# robot.net
KiCad netlist of a schematic drawn in EAGLE
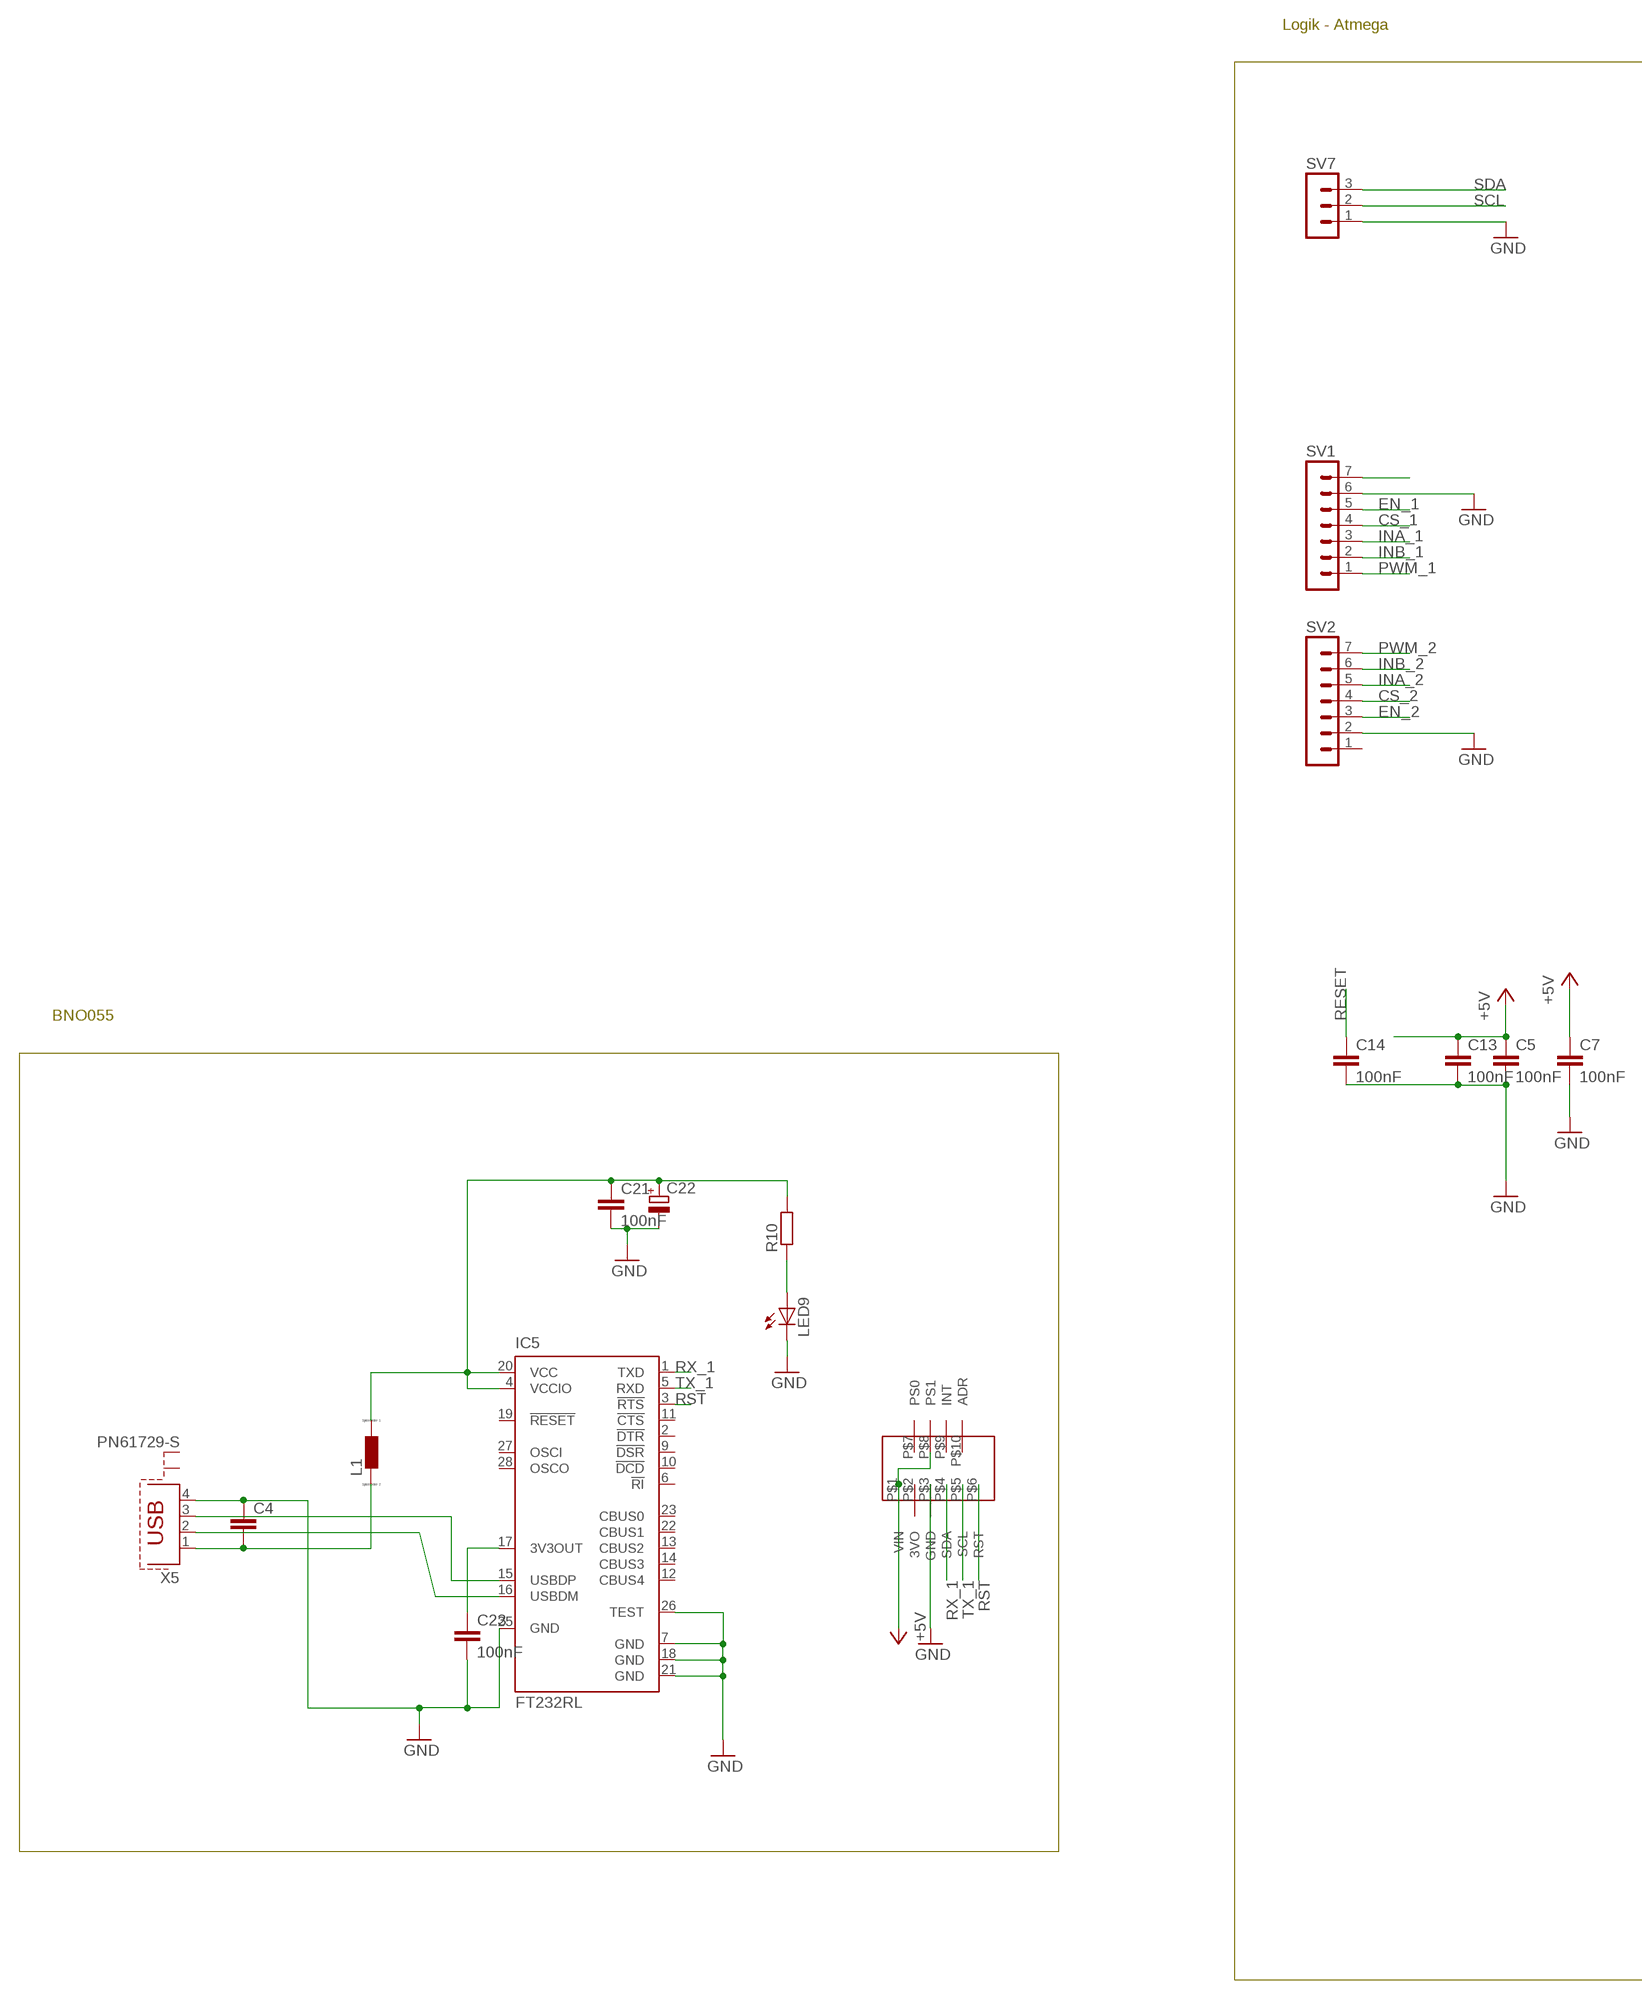
[diagram p0: schematic, sheet 1, part 1 of 3]
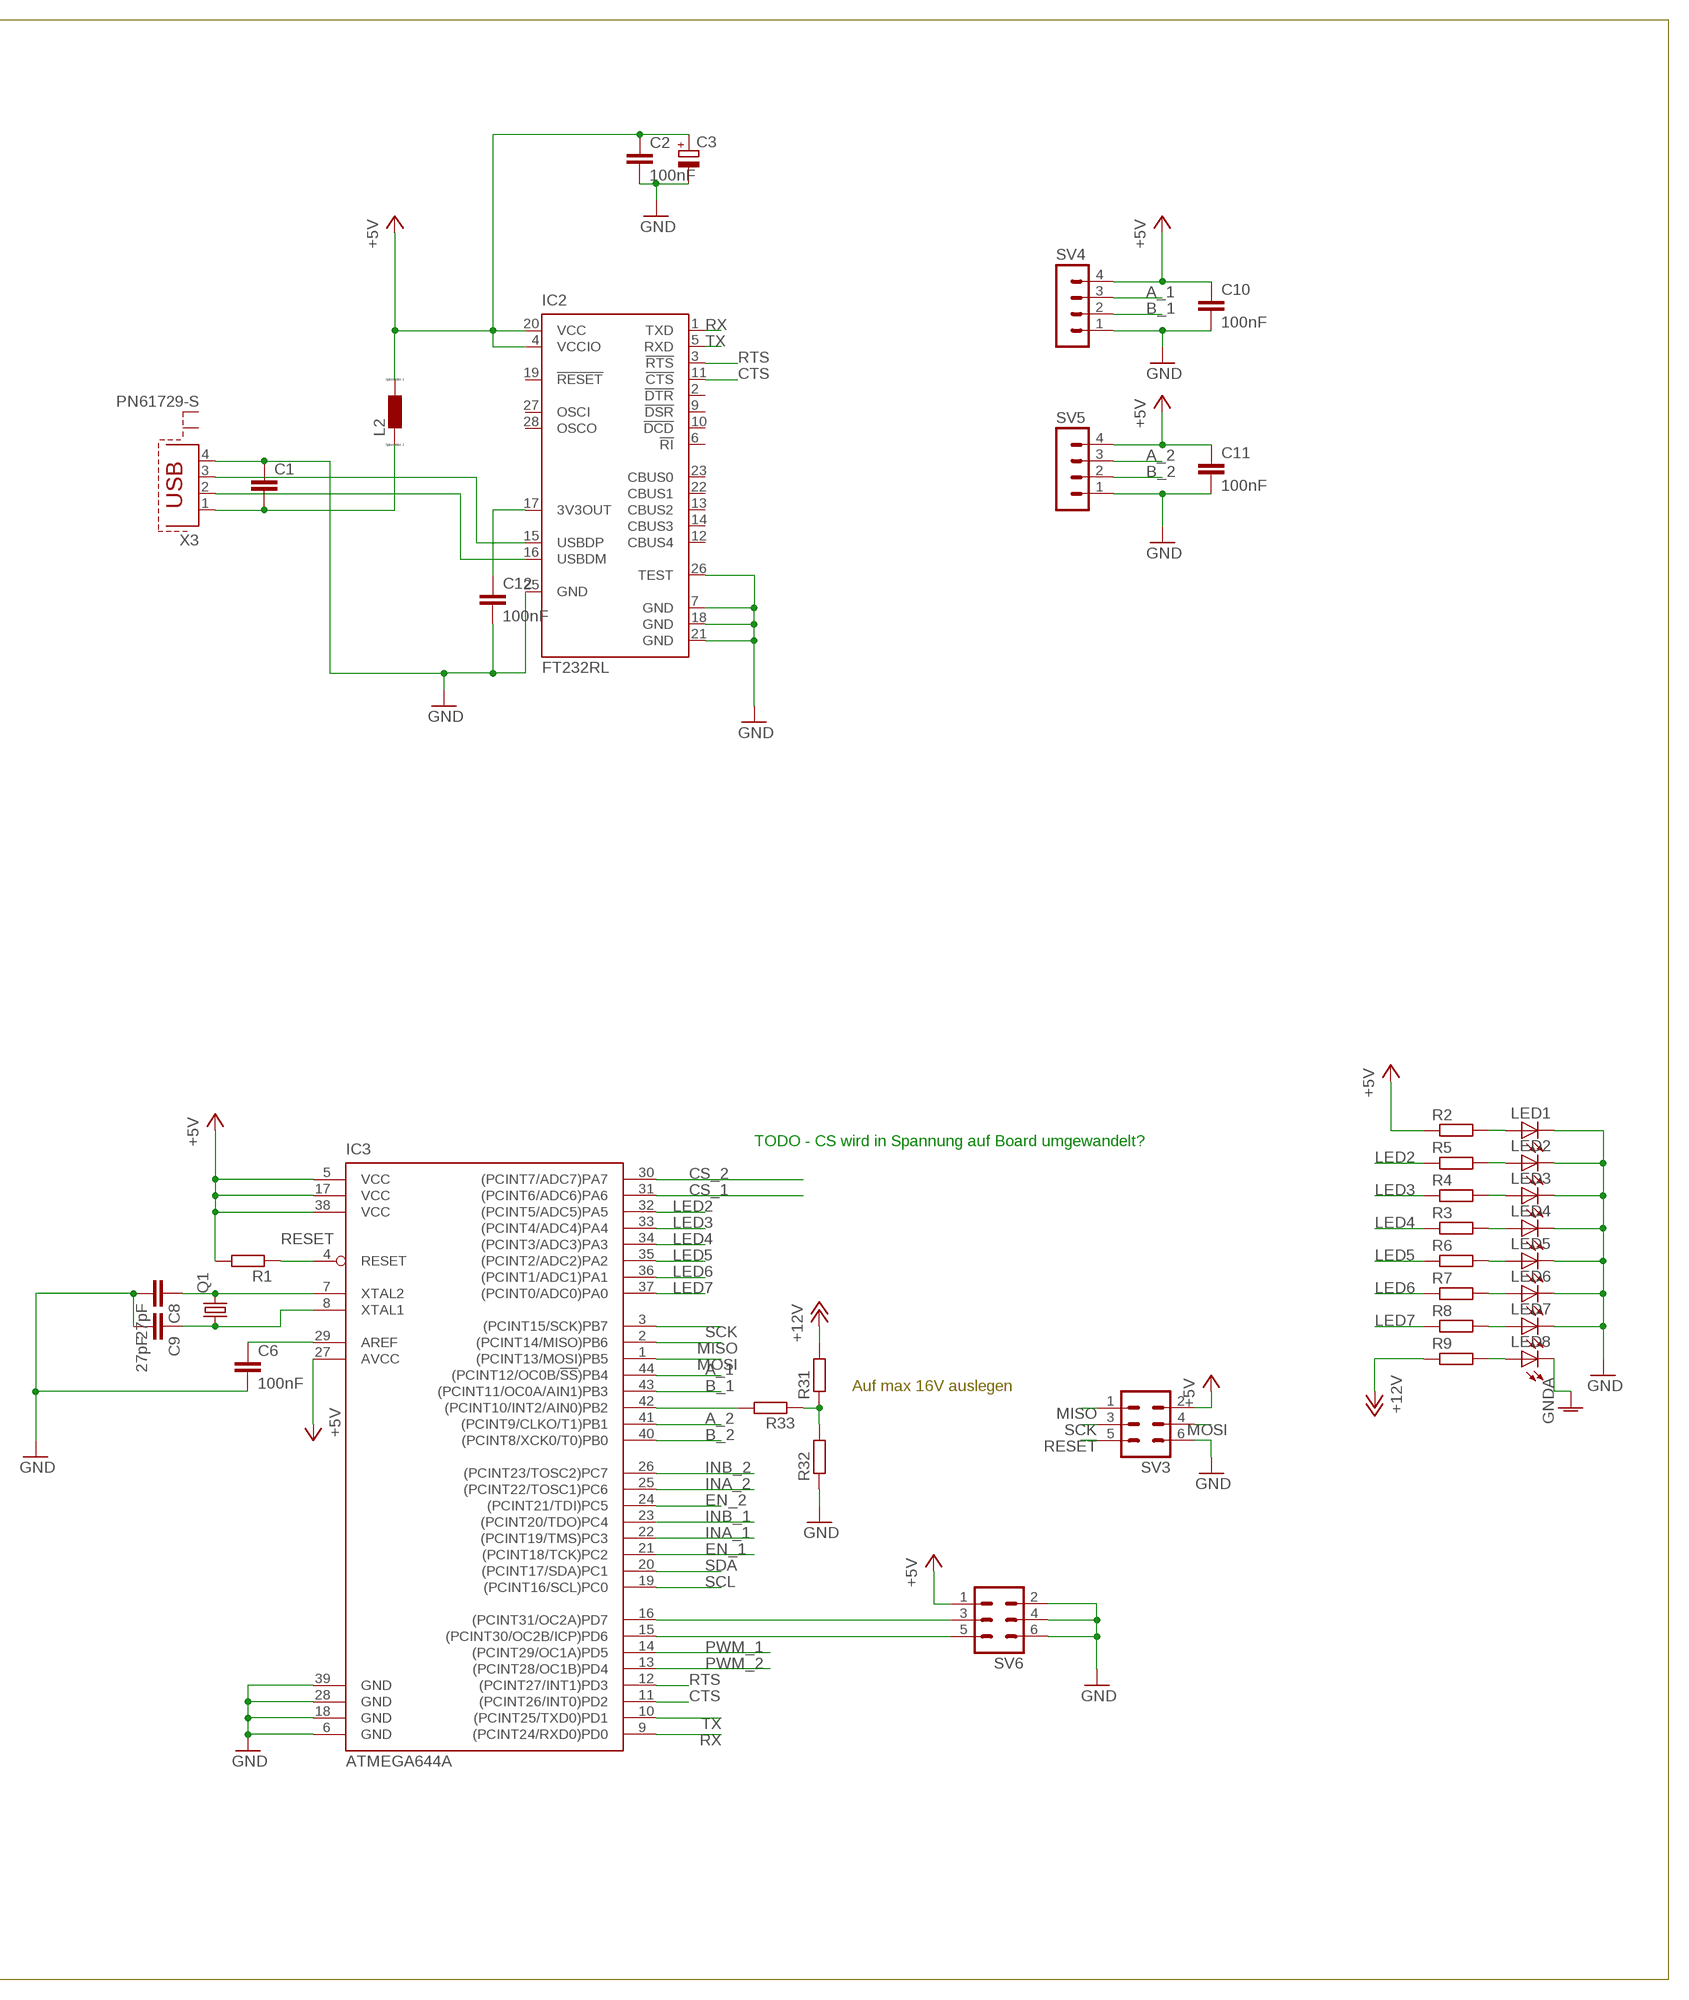
[diagram p1: schematic, sheet 1, part 2 of 3]
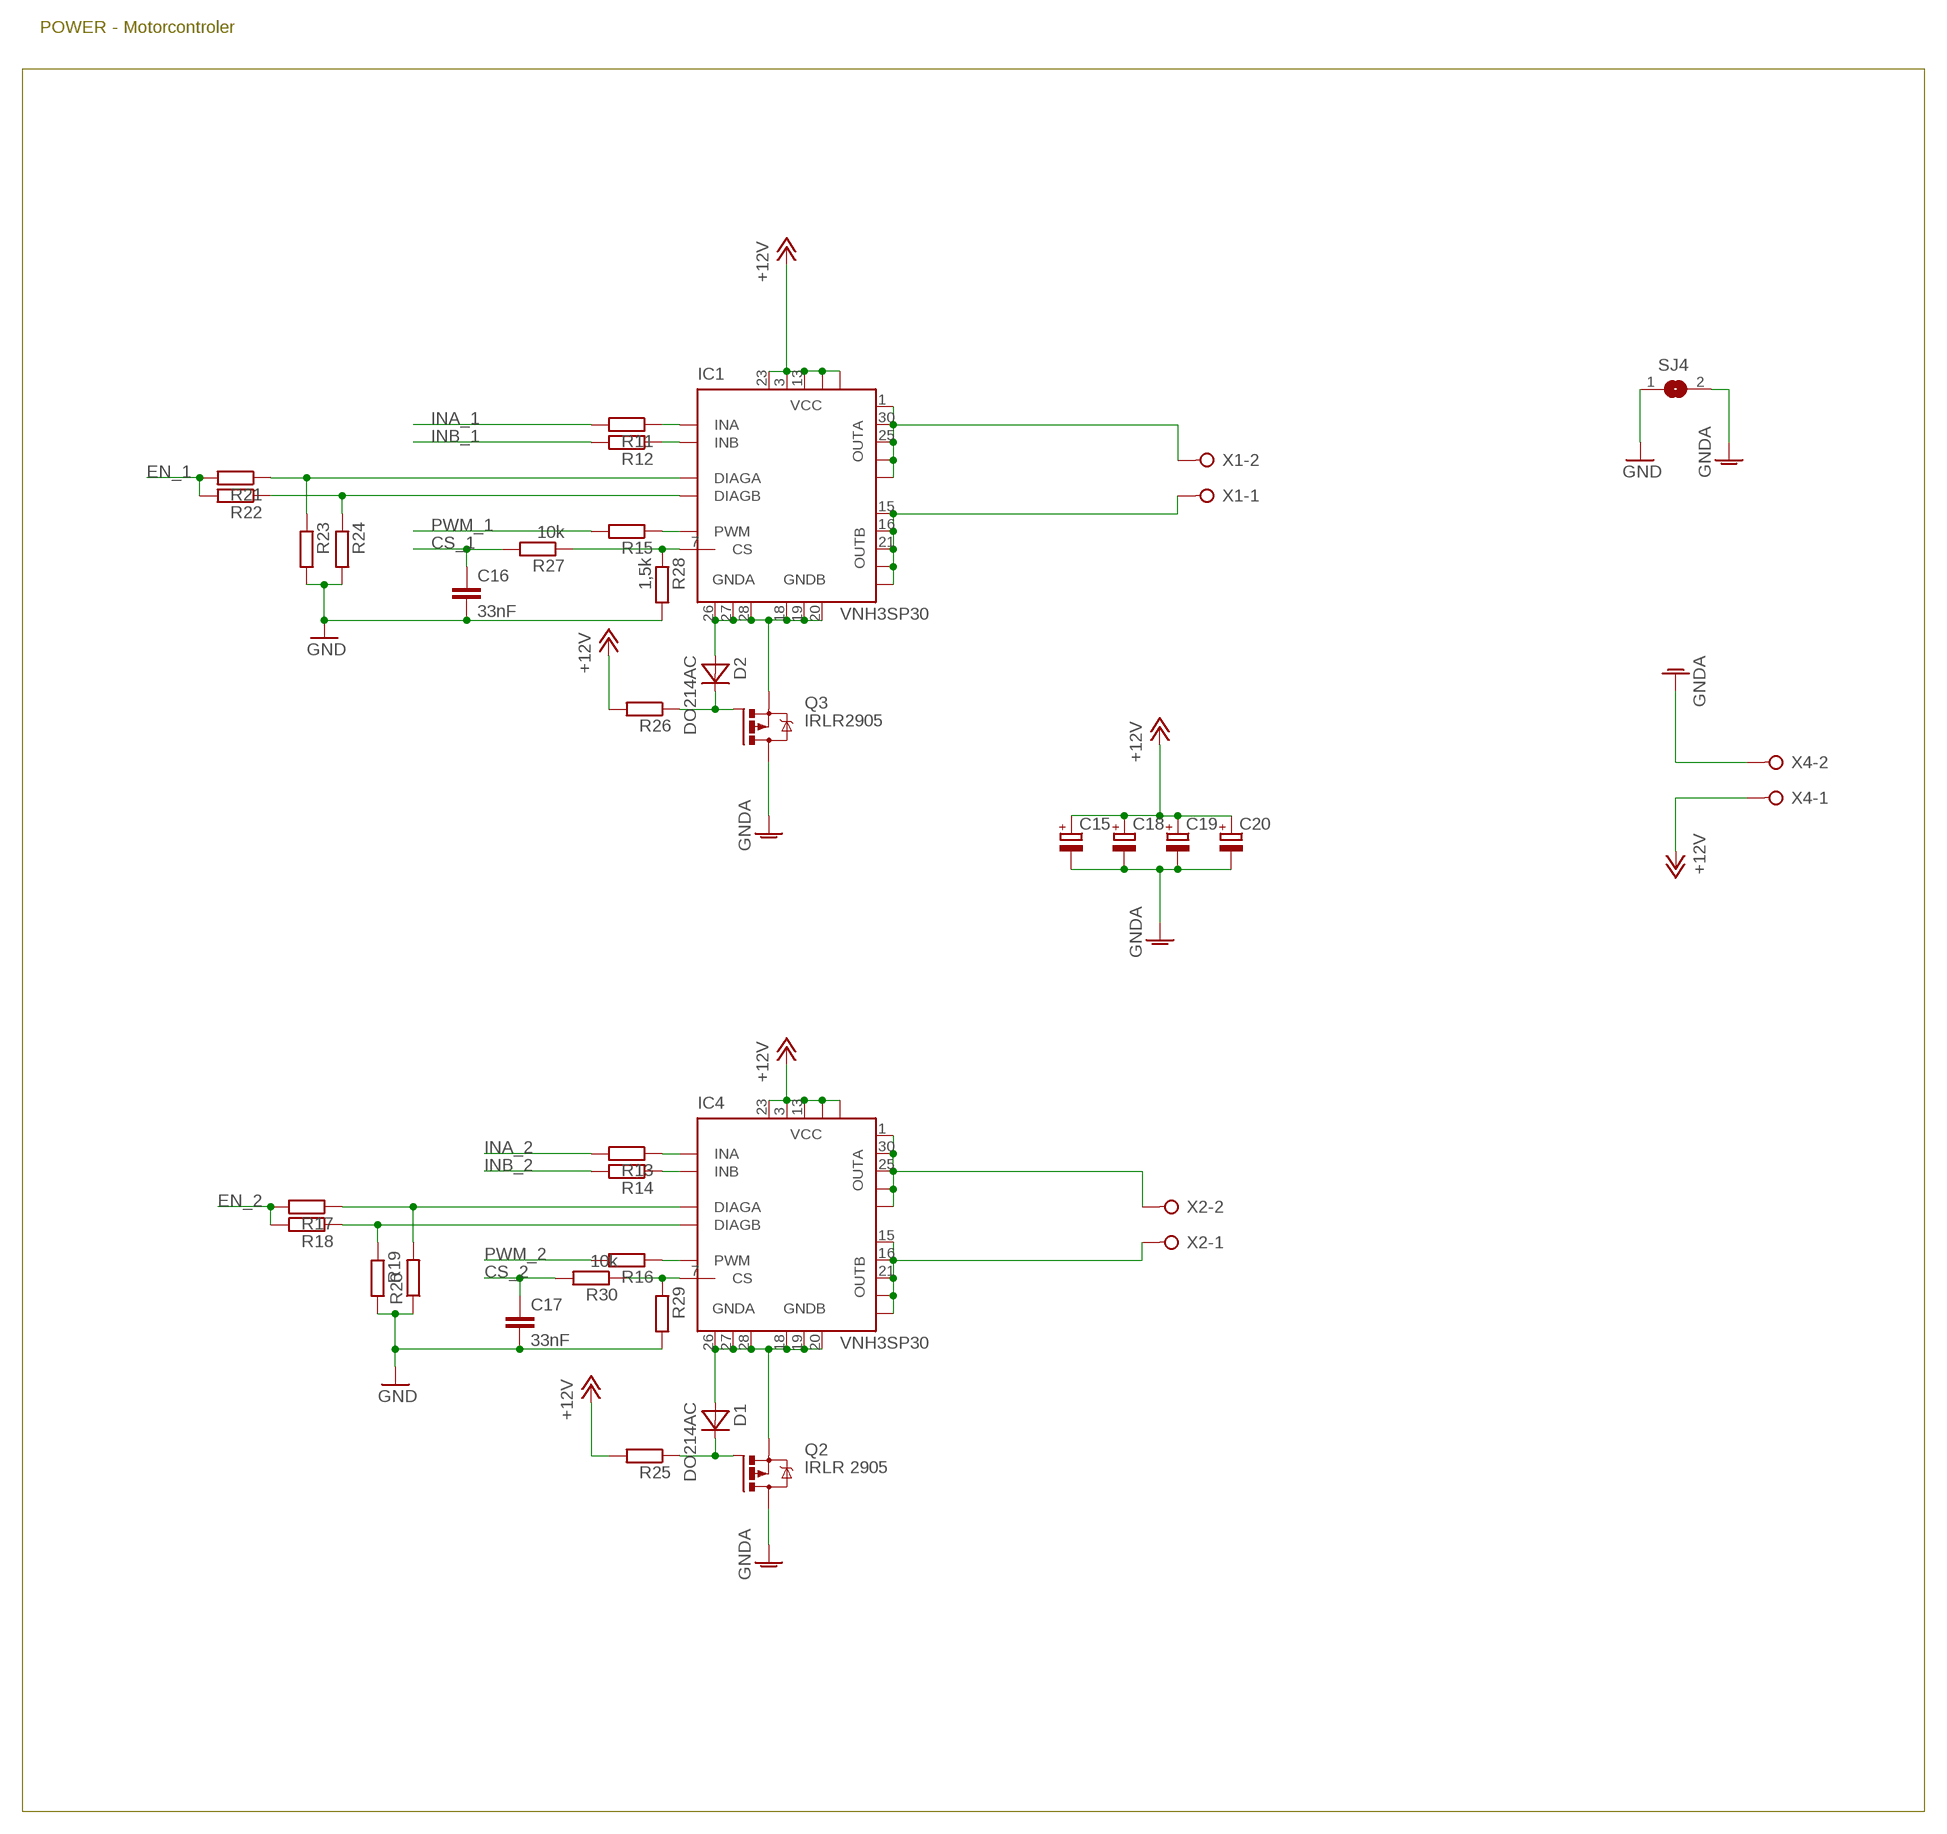
[diagram p2: schematic, sheet 1, part 3 of 3]

(export (version "E")
  (design (tool "Eeschema 10.0.6"))
  (components
    (comp (ref "C1")
      (value "C-EUC0805")
      (footprint "eagle-import:C0805")
      (libsource (lib "eagle-import") (part "C-EUC0805"))
    )
    (comp (ref "C2")
      (value "100nF")
      (footprint "eagle-import:C0805")
      (libsource (lib "eagle-import") (part "C-EUC0805"))
    )
    (comp (ref "C3")
      (value "CPOL-EU153CLV-0810")
      (footprint "eagle-import:153CLV-0810")
      (libsource (lib "eagle-import") (part "CPOL-EU153CLV-0810"))
    )
    (comp (ref "C4")
      (value "C-EUC0805")
      (footprint "eagle-import:C0805")
      (libsource (lib "eagle-import") (part "C-EUC0805"))
    )
    (comp (ref "C5")
      (value "100nF")
      (footprint "eagle-import:C0805")
      (libsource (lib "eagle-import") (part "C-EUC0805"))
    )
    (comp (ref "C6")
      (value "100nF")
      (footprint "eagle-import:C0805")
      (libsource (lib "eagle-import") (part "C-EUC0805"))
    )
    (comp (ref "C7")
      (value "100nF")
      (footprint "eagle-import:C0805")
      (libsource (lib "eagle-import") (part "C-EUC0805"))
    )
    (comp (ref "C8")
      (value "27pF")
      (footprint "eagle-import:C0805")
      (libsource (lib "eagle-import") (part "C-EUC0805"))
    )
    (comp (ref "C9")
      (value "27pF")
      (footprint "eagle-import:C0805")
      (libsource (lib "eagle-import") (part "C-EUC0805"))
    )
    (comp (ref "C10")
      (value "100nF")
      (footprint "eagle-import:C0805")
      (libsource (lib "eagle-import") (part "C-EUC0805"))
    )
    (comp (ref "C11")
      (value "100nF")
      (footprint "eagle-import:C0805")
      (libsource (lib "eagle-import") (part "C-EUC0805"))
    )
    (comp (ref "C12")
      (value "100nF")
      (footprint "eagle-import:C0805")
      (libsource (lib "eagle-import") (part "C-EUC0805"))
    )
    (comp (ref "C13")
      (value "100nF")
      (footprint "eagle-import:C0805")
      (libsource (lib "eagle-import") (part "C-EUC0805"))
    )
    (comp (ref "C14")
      (value "100nF")
      (footprint "eagle-import:C0805")
      (libsource (lib "eagle-import") (part "C-EUC0805"))
    )
    (comp (ref "C15")
      (value "CPOL-EU153CLV-0810")
      (footprint "eagle-import:153CLV-0810")
      (libsource (lib "eagle-import") (part "CPOL-EU153CLV-0810"))
    )
    (comp (ref "C16")
      (value "33nF")
      (footprint "eagle-import:C0805")
      (libsource (lib "eagle-import") (part "C-EUC0805"))
    )
    (comp (ref "C17")
      (value "33nF")
      (footprint "eagle-import:C0805")
      (libsource (lib "eagle-import") (part "C-EUC0805"))
    )
    (comp (ref "C18")
      (value "CPOL-EU153CLV-0810")
      (footprint "eagle-import:153CLV-0810")
      (libsource (lib "eagle-import") (part "CPOL-EU153CLV-0810"))
    )
    (comp (ref "C19")
      (value "CPOL-EU153CLV-0810")
      (footprint "eagle-import:153CLV-0810")
      (libsource (lib "eagle-import") (part "CPOL-EU153CLV-0810"))
    )
    (comp (ref "C20")
      (value "CPOL-EU153CLV-0810")
      (footprint "eagle-import:153CLV-0810")
      (libsource (lib "eagle-import") (part "CPOL-EU153CLV-0810"))
    )
    (comp (ref "C21")
      (value "100nF")
      (footprint "eagle-import:C0805")
      (libsource (lib "eagle-import") (part "C-EUC0805"))
    )
    (comp (ref "C22")
      (value "CPOL-EU153CLV-0810")
      (footprint "eagle-import:153CLV-0810")
      (libsource (lib "eagle-import") (part "CPOL-EU153CLV-0810"))
    )
    (comp (ref "C23")
      (value "100nF")
      (footprint "eagle-import:C0805")
      (libsource (lib "eagle-import") (part "C-EUC0805"))
    )
    (comp (ref "D1")
      (value "DO214AC")
      (footprint "eagle-import:SMA")
      (libsource (lib "eagle-import") (part "MBRA340T3"))
    )
    (comp (ref "D2")
      (value "DO214AC")
      (footprint "eagle-import:SMA")
      (libsource (lib "eagle-import") (part "MBRA340T3"))
    )
    (comp (ref "IC1")
      (value "VNH3SP30")
      (footprint "eagle-import:MULTIPOWERSO-30")
      (libsource (lib "eagle-import") (part "VNH3SP30"))
    )
    (comp (ref "IC2")
      (value "FT232RL")
      (footprint "eagle-import:SSOP28")
      (libsource (lib "eagle-import") (part "FT232RL"))
    )
    (comp (ref "IC3")
      (value "ATMEGA644A")
      (footprint "eagle-import:TQFP44")
      (fields (field (name "MPN") "ATMEGA644PV-10AU"))
      (libsource (lib "eagle-import") (part "ATMEGA644A"))
    )
    (comp (ref "IC4")
      (value "VNH3SP30")
      (footprint "eagle-import:MULTIPOWERSO-30")
      (libsource (lib "eagle-import") (part "VNH3SP30"))
    )
    (comp (ref "IC5")
      (value "FT232RL")
      (footprint "eagle-import:SSOP28")
      (libsource (lib "eagle-import") (part "FT232RL"))
    )
    (comp (ref "L1")
      (value "LL4532C")
      (footprint "eagle-import:L4532M")
      (libsource (lib "eagle-import") (part "LL4532C"))
    )
    (comp (ref "L2")
      (value "LL4532C")
      (footprint "eagle-import:L4532M")
      (libsource (lib "eagle-import") (part "LL4532C"))
    )
    (comp (ref "LED1")
      (value "LEDCHIPLED_0805")
      (footprint "eagle-import:CHIPLED_0805")
      (libsource (lib "eagle-import") (part "LEDCHIPLED_0805"))
    )
    (comp (ref "LED2")
      (value "LEDCHIPLED_0805")
      (footprint "eagle-import:CHIPLED_0805")
      (libsource (lib "eagle-import") (part "LEDCHIPLED_0805"))
    )
    (comp (ref "LED3")
      (value "LEDCHIPLED_0805")
      (footprint "eagle-import:CHIPLED_0805")
      (libsource (lib "eagle-import") (part "LEDCHIPLED_0805"))
    )
    (comp (ref "LED4")
      (value "LEDCHIPLED_0805")
      (footprint "eagle-import:CHIPLED_0805")
      (libsource (lib "eagle-import") (part "LEDCHIPLED_0805"))
    )
    (comp (ref "LED5")
      (value "LEDCHIPLED_0805")
      (footprint "eagle-import:CHIPLED_0805")
      (libsource (lib "eagle-import") (part "LEDCHIPLED_0805"))
    )
    (comp (ref "LED6")
      (value "LEDCHIPLED_0805")
      (footprint "eagle-import:CHIPLED_0805")
      (libsource (lib "eagle-import") (part "LEDCHIPLED_0805"))
    )
    (comp (ref "LED7")
      (value "LEDCHIPLED_0805")
      (footprint "eagle-import:CHIPLED_0805")
      (libsource (lib "eagle-import") (part "LEDCHIPLED_0805"))
    )
    (comp (ref "LED8")
      (value "LEDCHIPLED_0805")
      (footprint "eagle-import:CHIPLED_0805")
      (libsource (lib "eagle-import") (part "LEDCHIPLED_0805"))
    )
    (comp (ref "LED9")
      (value "LEDCHIPLED_0805")
      (footprint "eagle-import:CHIPLED_0805")
      (libsource (lib "eagle-import") (part "LEDCHIPLED_0805"))
    )
    (comp (ref "Q1")
      (value "CRYSTALHC49UP")
      (footprint "eagle-import:HC49UP")
      (libsource (lib "eagle-import") (part "CRYSTALHC49UP"))
    )
    (comp (ref "Q2")
      (value "IRLR 2905")
      (footprint "eagle-import:D-PAK_TO252AA")
      (libsource (lib "eagle-import") (part "IRF?5305R"))
    )
    (comp (ref "Q3")
      (value "IRLR2905")
      (footprint "eagle-import:D-PAK_TO252AA")
      (libsource (lib "eagle-import") (part "IRF?5305R"))
    )
    (comp (ref "R1")
      (value "R-EU_M0805")
      (footprint "eagle-import:M0805")
      (libsource (lib "eagle-import") (part "R-EU_M0805"))
    )
    (comp (ref "R2")
      (value "R-EU_M0805")
      (footprint "eagle-import:M0805")
      (libsource (lib "eagle-import") (part "R-EU_M0805"))
    )
    (comp (ref "R3")
      (value "R-EU_M0805")
      (footprint "eagle-import:M0805")
      (libsource (lib "eagle-import") (part "R-EU_M0805"))
    )
    (comp (ref "R4")
      (value "R-EU_M0805")
      (footprint "eagle-import:M0805")
      (libsource (lib "eagle-import") (part "R-EU_M0805"))
    )
    (comp (ref "R5")
      (value "R-EU_M0805")
      (footprint "eagle-import:M0805")
      (libsource (lib "eagle-import") (part "R-EU_M0805"))
    )
    (comp (ref "R6")
      (value "R-EU_M0805")
      (footprint "eagle-import:M0805")
      (libsource (lib "eagle-import") (part "R-EU_M0805"))
    )
    (comp (ref "R7")
      (value "R-EU_M0805")
      (footprint "eagle-import:M0805")
      (libsource (lib "eagle-import") (part "R-EU_M0805"))
    )
    (comp (ref "R8")
      (value "R-EU_M0805")
      (footprint "eagle-import:M0805")
      (libsource (lib "eagle-import") (part "R-EU_M0805"))
    )
    (comp (ref "R9")
      (value "R-EU_M0805")
      (footprint "eagle-import:M0805")
      (libsource (lib "eagle-import") (part "R-EU_M0805"))
    )
    (comp (ref "R10")
      (value "R-EU_M0805")
      (footprint "eagle-import:M0805")
      (libsource (lib "eagle-import") (part "R-EU_M0805"))
    )
    (comp (ref "R11")
      (value "R-EU_M0805")
      (footprint "eagle-import:M0805")
      (libsource (lib "eagle-import") (part "R-EU_M0805"))
    )
    (comp (ref "R12")
      (value "R-EU_M0805")
      (footprint "eagle-import:M0805")
      (libsource (lib "eagle-import") (part "R-EU_M0805"))
    )
    (comp (ref "R13")
      (value "R-EU_M0805")
      (footprint "eagle-import:M0805")
      (libsource (lib "eagle-import") (part "R-EU_M0805"))
    )
    (comp (ref "R14")
      (value "R-EU_M0805")
      (footprint "eagle-import:M0805")
      (libsource (lib "eagle-import") (part "R-EU_M0805"))
    )
    (comp (ref "R15")
      (value "R-EU_M0805")
      (footprint "eagle-import:M0805")
      (libsource (lib "eagle-import") (part "R-EU_M0805"))
    )
    (comp (ref "R16")
      (value "R-EU_M0805")
      (footprint "eagle-import:M0805")
      (libsource (lib "eagle-import") (part "R-EU_M0805"))
    )
    (comp (ref "R17")
      (value "R-EU_M0805")
      (footprint "eagle-import:M0805")
      (libsource (lib "eagle-import") (part "R-EU_M0805"))
    )
    (comp (ref "R18")
      (value "R-EU_M0805")
      (footprint "eagle-import:M0805")
      (libsource (lib "eagle-import") (part "R-EU_M0805"))
    )
    (comp (ref "R19")
      (value "R-EU_M0805")
      (footprint "eagle-import:M0805")
      (libsource (lib "eagle-import") (part "R-EU_M0805"))
    )
    (comp (ref "R20")
      (value "R-EU_M0805")
      (footprint "eagle-import:M0805")
      (libsource (lib "eagle-import") (part "R-EU_M0805"))
    )
    (comp (ref "R21")
      (value "R-EU_M0805")
      (footprint "eagle-import:M0805")
      (libsource (lib "eagle-import") (part "R-EU_M0805"))
    )
    (comp (ref "R22")
      (value "R-EU_M0805")
      (footprint "eagle-import:M0805")
      (libsource (lib "eagle-import") (part "R-EU_M0805"))
    )
    (comp (ref "R23")
      (value "R-EU_M0805")
      (footprint "eagle-import:M0805")
      (libsource (lib "eagle-import") (part "R-EU_M0805"))
    )
    (comp (ref "R24")
      (value "R-EU_M0805")
      (footprint "eagle-import:M0805")
      (libsource (lib "eagle-import") (part "R-EU_M0805"))
    )
    (comp (ref "R25")
      (value "R-EU_M0805")
      (footprint "eagle-import:M0805")
      (libsource (lib "eagle-import") (part "R-EU_M0805"))
    )
    (comp (ref "R26")
      (value "R-EU_M0805")
      (footprint "eagle-import:M0805")
      (libsource (lib "eagle-import") (part "R-EU_M0805"))
    )
    (comp (ref "R27")
      (value "10k")
      (footprint "eagle-import:M0805")
      (libsource (lib "eagle-import") (part "R-EU_M0805"))
    )
    (comp (ref "R28")
      (value "1,5k")
      (footprint "eagle-import:M0805")
      (libsource (lib "eagle-import") (part "R-EU_M0805"))
    )
    (comp (ref "R29")
      (value "R-EU_M0805")
      (footprint "eagle-import:M0805")
      (libsource (lib "eagle-import") (part "R-EU_M0805"))
    )
    (comp (ref "R30")
      (value "10k")
      (footprint "eagle-import:M0805")
      (libsource (lib "eagle-import") (part "R-EU_M0805"))
    )
    (comp (ref "R31")
      (value "R-EU_M0805")
      (footprint "eagle-import:M0805")
      (libsource (lib "eagle-import") (part "R-EU_M0805"))
    )
    (comp (ref "R32")
      (value "R-EU_M0805")
      (footprint "eagle-import:M0805")
      (libsource (lib "eagle-import") (part "R-EU_M0805"))
    )
    (comp (ref "R33")
      (value "R-EU_M0805")
      (footprint "eagle-import:M0805")
      (libsource (lib "eagle-import") (part "R-EU_M0805"))
    )
    (comp (ref "SJ4") (value "SJ") (footprint "eagle-import:SJ") (libsource (lib "eagle-import") (part "SJ")))
    (comp (ref "SV1")
      (value "MA07-1")
      (footprint "eagle-import:MA07-1")
      (libsource (lib "eagle-import") (part "MA07-1"))
    )
    (comp (ref "SV2")
      (value "MA07-1")
      (footprint "eagle-import:MA07-1")
      (libsource (lib "eagle-import") (part "MA07-1"))
    )
    (comp (ref "SV3")
      (value "ML6")
      (footprint "eagle-import:ML6")
      (libsource (lib "eagle-import") (part "ML6"))
    )
    (comp (ref "SV4")
      (value "MA04-1")
      (footprint "eagle-import:MA04-1")
      (libsource (lib "eagle-import") (part "MA04-1"))
    )
    (comp (ref "SV5")
      (value "MA04-1")
      (footprint "eagle-import:MA04-1")
      (libsource (lib "eagle-import") (part "MA04-1"))
    )
    (comp (ref "SV6")
      (value "ML6")
      (footprint "eagle-import:ML6")
      (libsource (lib "eagle-import") (part "con-harting-ml_149_ML6"))
    )
    (comp (ref "SV7")
      (value "MA03-1")
      (footprint "eagle-import:MA03-1")
      (libsource (lib "eagle-import") (part "MA03-1"))
    )
    (comp (ref "U$1")
      (value "BNO055")
      (footprint "eagle-import:BNO055_ADA")
      (libsource (lib "eagle-import") (part "BNO055"))
    )
    (comp (ref "X1")
      (value "W237-02P")
      (footprint "eagle-import:W237-132")
      (libsource (lib "eagle-import") (part "W237-02P"))
    )
    (comp (ref "X2")
      (value "W237-02P")
      (footprint "eagle-import:W237-132")
      (libsource (lib "eagle-import") (part "W237-02P"))
    )
    (comp (ref "X3")
      (value "PN61729-S")
      (footprint "eagle-import:PN61729-S")
      (libsource (lib "eagle-import") (part "PN61729-S"))
    )
    (comp (ref "X4")
      (value "W237-02P")
      (footprint "eagle-import:W237-132")
      (libsource (lib "eagle-import") (part "W237-02P"))
    )
    (comp (ref "X5")
      (value "PN61729-S")
      (footprint "eagle-import:PN61729-S")
      (libsource (lib "eagle-import") (part "PN61729-S"))
    )
  )
  (nets
    (net (code "1") (name "+5V") (class "Default")
      (node (ref "C10") (pin "1") (pinfunction "1_1") (pintype "passive"))
      (node (ref "C11") (pin "1") (pinfunction "1_1") (pintype "passive"))
      (node (ref "C13") (pin "1") (pinfunction "1_1") (pintype "passive"))
      (node (ref "C2") (pin "1") (pinfunction "1_1") (pintype "passive"))
      (node (ref "C3") (pin "+") (pinfunction "+_+") (pintype "passive"))
      (node (ref "C5") (pin "1") (pinfunction "1_1") (pintype "passive"))
      (node (ref "C7") (pin "1") (pinfunction "1_1") (pintype "passive"))
      (node (ref "IC2") (pin "20") (pinfunction "VCC_20") (pintype "power_in"))
      (node (ref "IC2") (pin "4") (pinfunction "VCCIO_4") (pintype "power_in"))
      (node (ref "IC3") (pin "17") (pinfunction "VCC_17") (pintype "power_in"))
      (node (ref "IC3") (pin "27") (pinfunction "AVCC_27") (pintype "power_in"))
      (node (ref "IC3") (pin "38") (pinfunction "VCC_38") (pintype "power_in"))
      (node (ref "IC3") (pin "5") (pinfunction "VCC_5") (pintype "power_in"))
      (node (ref "L2") (pin "1") (pinfunction "1_1") (pintype "passive"))
      (node (ref "R1") (pin "2") (pinfunction "2_2") (pintype "passive"))
      (node (ref "R2") (pin "1") (pinfunction "1_1") (pintype "passive"))
      (node (ref "SV3") (pin "2") (pinfunction "2_2") (pintype "passive"))
      (node (ref "SV4") (pin "4") (pinfunction "4_4") (pintype "passive"))
      (node (ref "SV5") (pin "4") (pinfunction "4_4") (pintype "passive"))
      (node (ref "SV6") (pin "1") (pinfunction "1_1") (pintype "passive"))
      (node (ref "U$1") (pin "P$1") (pinfunction "VIN_P$1") (pintype "bidirectional"))
      (node (ref "U$1") (pin "P$8") (pinfunction "PS1_P$8") (pintype "bidirectional"))
    )
    (net (code "2") (name "+12V") (class "Default")
      (node (ref "C15") (pin "+") (pinfunction "+_+") (pintype "passive"))
      (node (ref "C18") (pin "+") (pinfunction "+_+") (pintype "passive"))
      (node (ref "C19") (pin "+") (pinfunction "+_+") (pintype "passive"))
      (node (ref "C20") (pin "+") (pinfunction "+_+") (pintype "passive"))
      (node (ref "IC1") (pin "13") (pinfunction "VCC_13") (pintype "power_in"))
      (node (ref "IC1") (pin "23") (pinfunction "VCC_23") (pintype "power_in"))
      (node (ref "IC1") (pin "3") (pinfunction "VCC_3") (pintype "power_in"))
      (node (ref "IC1") (pin "VCC") (pinfunction "VCC_VCC") (pintype "power_in"))
      (node (ref "IC1") (pin "VCC@1") (pinfunction "VCC_VCC@1") (pintype "power_in"))
      (node (ref "IC4") (pin "13") (pinfunction "VCC_13") (pintype "power_in"))
      (node (ref "IC4") (pin "23") (pinfunction "VCC_23") (pintype "power_in"))
      (node (ref "IC4") (pin "3") (pinfunction "VCC_3") (pintype "power_in"))
      (node (ref "IC4") (pin "VCC") (pinfunction "VCC_VCC") (pintype "power_in"))
      (node (ref "IC4") (pin "VCC@1") (pinfunction "VCC_VCC@1") (pintype "power_in"))
      (node (ref "R25") (pin "2") (pinfunction "2_2") (pintype "passive"))
      (node (ref "R26") (pin "2") (pinfunction "2_2") (pintype "passive"))
      (node (ref "R31") (pin "2") (pinfunction "2_2") (pintype "passive"))
      (node (ref "R9") (pin "1") (pinfunction "1_1") (pintype "passive"))
      (node (ref "X4") (pin "1") (pinfunction "KL_1") (pintype "passive"))
    )
    (net (code "3") (name "/A_1") (class "Default")
      (node (ref "IC3") (pin "44") (pinfunction "(PCINT12/OC0B/~{SS})PB4_44") (pintype "bidirectional"))
      (node (ref "SV4") (pin "3") (pinfunction "3_3") (pintype "passive"))
    )
    (net (code "4") (name "/A_2") (class "Default")
      (node (ref "IC3") (pin "41") (pinfunction "(PCINT9/CLKO/T1)PB1_41") (pintype "bidirectional"))
      (node (ref "SV5") (pin "3") (pinfunction "3_3") (pintype "passive"))
    )
    (net (code "5") (name "/B_1") (class "Default")
      (node (ref "IC3") (pin "43") (pinfunction "(PCINT11/OC0A/AIN1)PB3_43") (pintype "bidirectional"))
      (node (ref "SV4") (pin "2") (pinfunction "2_2") (pintype "passive"))
    )
    (net (code "6") (name "/B_2") (class "Default")
      (node (ref "IC3") (pin "40") (pinfunction "(PCINT8/XCK0/T0)PB0_40") (pintype "bidirectional"))
      (node (ref "SV5") (pin "2") (pinfunction "2_2") (pintype "passive"))
    )
    (net (code "7") (name "/CS_1") (class "Default")
      (node (ref "C16") (pin "1") (pinfunction "1_1") (pintype "passive"))
      (node (ref "IC3") (pin "31") (pinfunction "(PCINT6/ADC6)PA6_31") (pintype "bidirectional"))
      (node (ref "R27") (pin "2") (pinfunction "2_2") (pintype "passive"))
      (node (ref "SV1") (pin "4") (pinfunction "4_4") (pintype "passive"))
    )
    (net (code "8") (name "/CS_2") (class "Default")
      (node (ref "C17") (pin "1") (pinfunction "1_1") (pintype "passive"))
      (node (ref "IC3") (pin "30") (pinfunction "(PCINT7/ADC7)PA7_30") (pintype "bidirectional"))
      (node (ref "R30") (pin "2") (pinfunction "2_2") (pintype "passive"))
      (node (ref "SV2") (pin "4") (pinfunction "4_4") (pintype "passive"))
    )
    (net (code "9") (name "/CTS") (class "Default")
      (node (ref "IC2") (pin "11") (pinfunction "~{CTS}_11") (pintype "input"))
      (node (ref "IC3") (pin "11") (pinfunction "(PCINT26/INT0)PD2_11") (pintype "bidirectional"))
    )
    (net (code "10") (name "/EN_1") (class "Default")
      (node (ref "IC3") (pin "21") (pinfunction "(PCINT18/TCK)PC2_21") (pintype "output"))
      (node (ref "R21") (pin "2") (pinfunction "2_2") (pintype "passive"))
      (node (ref "R22") (pin "2") (pinfunction "2_2") (pintype "passive"))
      (node (ref "SV1") (pin "5") (pinfunction "5_5") (pintype "passive"))
    )
    (net (code "11") (name "/EN_2") (class "Default")
      (node (ref "IC3") (pin "24") (pinfunction "(PCINT21/TDI)PC5_24") (pintype "output"))
      (node (ref "R17") (pin "2") (pinfunction "2_2") (pintype "passive"))
      (node (ref "R18") (pin "2") (pinfunction "2_2") (pintype "passive"))
      (node (ref "SV2") (pin "3") (pinfunction "3_3") (pintype "passive"))
    )
    (net (code "12") (name "/INA_1") (class "Default")
      (node (ref "IC3") (pin "22") (pinfunction "(PCINT19/TMS)PC3_22") (pintype "output"))
      (node (ref "R11") (pin "2") (pinfunction "2_2") (pintype "passive"))
      (node (ref "SV1") (pin "3") (pinfunction "3_3") (pintype "passive"))
    )
    (net (code "13") (name "/INA_2") (class "Default")
      (node (ref "IC3") (pin "25") (pinfunction "(PCINT22/TOSC1)PC6_25") (pintype "output"))
      (node (ref "R13") (pin "2") (pinfunction "2_2") (pintype "passive"))
      (node (ref "SV2") (pin "5") (pinfunction "5_5") (pintype "passive"))
    )
    (net (code "14") (name "/INB_1") (class "Default")
      (node (ref "IC3") (pin "23") (pinfunction "(PCINT20/TDO)PC4_23") (pintype "output"))
      (node (ref "R12") (pin "2") (pinfunction "2_2") (pintype "passive"))
      (node (ref "SV1") (pin "2") (pinfunction "2_2") (pintype "passive"))
    )
    (net (code "15") (name "/INB_2") (class "Default")
      (node (ref "IC3") (pin "26") (pinfunction "(PCINT23/TOSC2)PC7_26") (pintype "output"))
      (node (ref "R14") (pin "2") (pinfunction "2_2") (pintype "passive"))
      (node (ref "SV2") (pin "6") (pinfunction "6_6") (pintype "passive"))
    )
    (net (code "16") (name "/LED2") (class "Default")
      (node (ref "IC3") (pin "32") (pinfunction "(PCINT5/ADC5)PA5_32") (pintype "bidirectional"))
      (node (ref "R5") (pin "1") (pinfunction "1_1") (pintype "passive"))
    )
    (net (code "17") (name "/LED3") (class "Default")
      (node (ref "IC3") (pin "33") (pinfunction "(PCINT4/ADC4)PA4_33") (pintype "bidirectional"))
      (node (ref "R4") (pin "1") (pinfunction "1_1") (pintype "passive"))
    )
    (net (code "18") (name "/LED4") (class "Default")
      (node (ref "IC3") (pin "34") (pinfunction "(PCINT3/ADC3)PA3_34") (pintype "bidirectional"))
      (node (ref "R3") (pin "1") (pinfunction "1_1") (pintype "passive"))
    )
    (net (code "19") (name "/LED5") (class "Default")
      (node (ref "IC3") (pin "35") (pinfunction "(PCINT2/ADC2)PA2_35") (pintype "bidirectional"))
      (node (ref "R6") (pin "1") (pinfunction "1_1") (pintype "passive"))
    )
    (net (code "20") (name "/LED6") (class "Default")
      (node (ref "IC3") (pin "36") (pinfunction "(PCINT1/ADC1)PA1_36") (pintype "bidirectional"))
      (node (ref "R7") (pin "1") (pinfunction "1_1") (pintype "passive"))
    )
    (net (code "21") (name "/LED7") (class "Default")
      (node (ref "IC3") (pin "37") (pinfunction "(PCINT0/ADC0)PA0_37") (pintype "bidirectional"))
      (node (ref "R8") (pin "1") (pinfunction "1_1") (pintype "passive"))
    )
    (net (code "22") (name "/MISO") (class "Default")
      (node (ref "IC3") (pin "2") (pinfunction "(PCINT14/MISO)PB6_2") (pintype "bidirectional"))
      (node (ref "SV3") (pin "1") (pinfunction "1_1") (pintype "passive"))
    )
    (net (code "23") (name "/MOSI") (class "Default")
      (node (ref "IC3") (pin "1") (pinfunction "(PCINT13/MOSI)PB5_1") (pintype "bidirectional"))
      (node (ref "SV3") (pin "4") (pinfunction "4_4") (pintype "passive"))
    )
    (net (code "24") (name "/PWM_1") (class "Default")
      (node (ref "IC3") (pin "14") (pinfunction "(PCINT29/OC1A)PD5_14") (pintype "bidirectional"))
      (node (ref "R15") (pin "2") (pinfunction "2_2") (pintype "passive"))
      (node (ref "SV1") (pin "1") (pinfunction "1_1") (pintype "passive"))
    )
    (net (code "25") (name "/PWM_2") (class "Default")
      (node (ref "IC3") (pin "13") (pinfunction "(PCINT28/OC1B)PD4_13") (pintype "bidirectional"))
      (node (ref "R16") (pin "2") (pinfunction "2_2") (pintype "passive"))
      (node (ref "SV2") (pin "7") (pinfunction "7_7") (pintype "passive"))
    )
    (net (code "26") (name "/RESET") (class "Default")
      (node (ref "C14") (pin "1") (pinfunction "1_1") (pintype "passive"))
      (node (ref "IC3") (pin "4") (pinfunction "RESET_4") (pintype "input"))
      (node (ref "R1") (pin "1") (pinfunction "1_1") (pintype "passive"))
      (node (ref "SV3") (pin "5") (pinfunction "5_5") (pintype "passive"))
    )
    (net (code "27") (name "/RST") (class "Default")
      (node (ref "IC5") (pin "3") (pinfunction "~{RTS}_3") (pintype "output"))
      (node (ref "U$1") (pin "P$6") (pinfunction "RST_P$6") (pintype "bidirectional"))
    )
    (net (code "28") (name "/RTS") (class "Default")
      (node (ref "IC2") (pin "3") (pinfunction "~{RTS}_3") (pintype "output"))
      (node (ref "IC3") (pin "12") (pinfunction "(PCINT27/INT1)PD3_12") (pintype "bidirectional"))
    )
    (net (code "29") (name "/RX") (class "Default")
      (node (ref "IC2") (pin "1") (pinfunction "TXD_1") (pintype "output"))
      (node (ref "IC3") (pin "9") (pinfunction "(PCINT24/RXD0)PD0_9") (pintype "bidirectional"))
    )
    (net (code "30") (name "/RX_1") (class "Default")
      (node (ref "IC5") (pin "1") (pinfunction "TXD_1") (pintype "output"))
      (node (ref "U$1") (pin "P$4") (pinfunction "SDA_P$4") (pintype "bidirectional"))
    )
    (net (code "31") (name "/SCK") (class "Default")
      (node (ref "IC3") (pin "3") (pinfunction "(PCINT15/SCK)PB7_3") (pintype "bidirectional"))
      (node (ref "SV3") (pin "3") (pinfunction "3_3") (pintype "passive"))
    )
    (net (code "32") (name "/SCL") (class "Default")
      (node (ref "IC3") (pin "19") (pinfunction "(PCINT16/SCL)PC0_19") (pintype "output"))
      (node (ref "SV7") (pin "2") (pinfunction "2_2") (pintype "passive"))
    )
    (net (code "33") (name "/SDA") (class "Default")
      (node (ref "IC3") (pin "20") (pinfunction "(PCINT17/SDA)PC1_20") (pintype "output"))
      (node (ref "SV7") (pin "3") (pinfunction "3_3") (pintype "passive"))
    )
    (net (code "34") (name "/TX") (class "Default")
      (node (ref "IC2") (pin "5") (pinfunction "RXD_5") (pintype "input"))
      (node (ref "IC3") (pin "10") (pinfunction "(PCINT25/TXD0)PD1_10") (pintype "bidirectional"))
    )
    (net (code "35") (name "/TX_1") (class "Default")
      (node (ref "IC5") (pin "5") (pinfunction "RXD_5") (pintype "input"))
      (node (ref "U$1") (pin "P$5") (pinfunction "SCL_P$5") (pintype "bidirectional"))
    )
    (net (code "36") (name "GND") (class "Default")
      (node (ref "C1") (pin "1") (pinfunction "1_1") (pintype "passive"))
      (node (ref "C10") (pin "2") (pinfunction "2_2") (pintype "passive"))
      (node (ref "C11") (pin "2") (pinfunction "2_2") (pintype "passive"))
      (node (ref "C12") (pin "2") (pinfunction "2_2") (pintype "passive"))
      (node (ref "C13") (pin "2") (pinfunction "2_2") (pintype "passive"))
      (node (ref "C14") (pin "2") (pinfunction "2_2") (pintype "passive"))
      (node (ref "C16") (pin "2") (pinfunction "2_2") (pintype "passive"))
      (node (ref "C17") (pin "2") (pinfunction "2_2") (pintype "passive"))
      (node (ref "C2") (pin "2") (pinfunction "2_2") (pintype "passive"))
      (node (ref "C21") (pin "2") (pinfunction "2_2") (pintype "passive"))
      (node (ref "C22") (pin "-") (pinfunction "-_-") (pintype "passive"))
      (node (ref "C23") (pin "2") (pinfunction "2_2") (pintype "passive"))
      (node (ref "C3") (pin "-") (pinfunction "-_-") (pintype "passive"))
      (node (ref "C4") (pin "1") (pinfunction "1_1") (pintype "passive"))
      (node (ref "C5") (pin "2") (pinfunction "2_2") (pintype "passive"))
      (node (ref "C6") (pin "2") (pinfunction "2_2") (pintype "passive"))
      (node (ref "C7") (pin "2") (pinfunction "2_2") (pintype "passive"))
      (node (ref "C8") (pin "2") (pinfunction "2_2") (pintype "passive"))
      (node (ref "C9") (pin "2") (pinfunction "2_2") (pintype "passive"))
      (node (ref "IC2") (pin "18") (pinfunction "GND_18") (pintype "power_in"))
      (node (ref "IC2") (pin "21") (pinfunction "GND_21") (pintype "power_in"))
      (node (ref "IC2") (pin "25") (pinfunction "GND_25") (pintype "power_in"))
      (node (ref "IC2") (pin "26") (pinfunction "TEST_26") (pintype "input"))
      (node (ref "IC2") (pin "7") (pinfunction "GND_7") (pintype "power_in"))
      (node (ref "IC3") (pin "18") (pinfunction "GND_18") (pintype "power_in"))
      (node (ref "IC3") (pin "28") (pinfunction "GND_28") (pintype "power_in"))
      (node (ref "IC3") (pin "39") (pinfunction "GND_39") (pintype "power_in"))
      (node (ref "IC3") (pin "6") (pinfunction "GND_6") (pintype "power_in"))
      (node (ref "IC5") (pin "18") (pinfunction "GND_18") (pintype "power_in"))
      (node (ref "IC5") (pin "21") (pinfunction "GND_21") (pintype "power_in"))
      (node (ref "IC5") (pin "25") (pinfunction "GND_25") (pintype "power_in"))
      (node (ref "IC5") (pin "26") (pinfunction "TEST_26") (pintype "input"))
      (node (ref "IC5") (pin "7") (pinfunction "GND_7") (pintype "power_in"))
      (node (ref "LED1") (pin "C") (pinfunction "C_C") (pintype "passive"))
      (node (ref "LED2") (pin "C") (pinfunction "C_C") (pintype "passive"))
      (node (ref "LED3") (pin "C") (pinfunction "C_C") (pintype "passive"))
      (node (ref "LED4") (pin "C") (pinfunction "C_C") (pintype "passive"))
      (node (ref "LED5") (pin "C") (pinfunction "C_C") (pintype "passive"))
      (node (ref "LED6") (pin "C") (pinfunction "C_C") (pintype "passive"))
      (node (ref "LED7") (pin "C") (pinfunction "C_C") (pintype "passive"))
      (node (ref "LED9") (pin "C") (pinfunction "C_C") (pintype "passive"))
      (node (ref "R19") (pin "2") (pinfunction "2_2") (pintype "passive"))
      (node (ref "R20") (pin "1") (pinfunction "1_1") (pintype "passive"))
      (node (ref "R23") (pin "2") (pinfunction "2_2") (pintype "passive"))
      (node (ref "R24") (pin "2") (pinfunction "2_2") (pintype "passive"))
      (node (ref "R28") (pin "2") (pinfunction "2_2") (pintype "passive"))
      (node (ref "R29") (pin "2") (pinfunction "2_2") (pintype "passive"))
      (node (ref "R32") (pin "1") (pinfunction "1_1") (pintype "passive"))
      (node (ref "SJ4") (pin "1") (pinfunction "1_1") (pintype "passive"))
      (node (ref "SV1") (pin "6") (pinfunction "6_6") (pintype "passive"))
      (node (ref "SV2") (pin "2") (pinfunction "2_2") (pintype "passive"))
      (node (ref "SV3") (pin "6") (pinfunction "6_6") (pintype "passive"))
      (node (ref "SV4") (pin "1") (pinfunction "1_1") (pintype "passive"))
      (node (ref "SV5") (pin "1") (pinfunction "1_1") (pintype "passive"))
      (node (ref "SV6") (pin "2") (pinfunction "2_2") (pintype "passive"))
      (node (ref "SV6") (pin "4") (pinfunction "4_4") (pintype "passive"))
      (node (ref "SV6") (pin "6") (pinfunction "6_6") (pintype "passive"))
      (node (ref "SV7") (pin "1") (pinfunction "1_1") (pintype "passive"))
      (node (ref "U$1") (pin "P$3") (pinfunction "GND_P$3") (pintype "bidirectional"))
      (node (ref "X3") (pin "4") (pinfunction "4_4") (pintype "passive"))
      (node (ref "X5") (pin "4") (pinfunction "4_4") (pintype "passive"))
    )
    (net (code "37") (name "GNDA") (class "Default")
      (node (ref "C15") (pin "-") (pinfunction "-_-") (pintype "passive"))
      (node (ref "C18") (pin "-") (pinfunction "-_-") (pintype "passive"))
      (node (ref "C19") (pin "-") (pinfunction "-_-") (pintype "passive"))
      (node (ref "C20") (pin "-") (pinfunction "-_-") (pintype "passive"))
      (node (ref "LED8") (pin "C") (pinfunction "C_C") (pintype "passive"))
      (node (ref "Q2") (pin "4") (pinfunction "D_4") (pintype "passive"))
      (node (ref "Q3") (pin "4") (pinfunction "D_4") (pintype "passive"))
      (node (ref "SJ4") (pin "2") (pinfunction "2_2") (pintype "passive"))
      (node (ref "X4") (pin "2") (pinfunction "KL_2") (pintype "passive"))
    )
    (net (code "38") (name "Net-(C1-Pad2)") (class "Default")
      (node (ref "C1") (pin "2") (pinfunction "2_2") (pintype "passive"))
      (node (ref "L2") (pin "2") (pinfunction "2_2") (pintype "passive"))
      (node (ref "X3") (pin "1") (pinfunction "1_1") (pintype "passive"))
    )
    (net (code "39") (name "Net-(C4-Pad2)") (class "Default")
      (node (ref "C4") (pin "2") (pinfunction "2_2") (pintype "passive"))
      (node (ref "L1") (pin "2") (pinfunction "2_2") (pintype "passive"))
      (node (ref "X5") (pin "1") (pinfunction "1_1") (pintype "passive"))
    )
    (net (code "40") (name "Net-(IC1-CS)") (class "Default")
      (node (ref "IC1") (pin "7") (pinfunction "CS_7") (pintype "bidirectional"))
      (node (ref "R27") (pin "1") (pinfunction "1_1") (pintype "passive"))
      (node (ref "R28") (pin "1") (pinfunction "1_1") (pintype "passive"))
    )
    (net (code "41") (name "Net-(IC1-DIAGA)") (class "Default")
      (node (ref "IC1") (pin "6") (pinfunction "DIAGA_6") (pintype "open_collector"))
      (node (ref "R21") (pin "1") (pinfunction "1_1") (pintype "passive"))
      (node (ref "R23") (pin "1") (pinfunction "1_1") (pintype "passive"))
    )
    (net (code "42") (name "Net-(IC1-DIAGB)") (class "Default")
      (node (ref "IC1") (pin "10") (pinfunction "DIAGB_10") (pintype "open_collector"))
      (node (ref "R22") (pin "1") (pinfunction "1_1") (pintype "passive"))
      (node (ref "R24") (pin "1") (pinfunction "1_1") (pintype "passive"))
    )
    (net (code "43") (name "Net-(IC1-INA)") (class "Default")
      (node (ref "IC1") (pin "5") (pinfunction "INA_5") (pintype "input"))
      (node (ref "R11") (pin "1") (pinfunction "1_1") (pintype "passive"))
    )
    (net (code "44") (name "Net-(IC1-INB)") (class "Default")
      (node (ref "IC1") (pin "11") (pinfunction "INB_11") (pintype "input"))
      (node (ref "R12") (pin "1") (pinfunction "1_1") (pintype "passive"))
    )
    (net (code "45") (name "Net-(IC1-PWM)") (class "Default")
      (node (ref "IC1") (pin "8") (pinfunction "PWM_8") (pintype "input"))
      (node (ref "R15") (pin "1") (pinfunction "1_1") (pintype "passive"))
    )
    (net (code "46") (name "Net-(IC2-3V3OUT)") (class "Default")
      (node (ref "C12") (pin "1") (pinfunction "1_1") (pintype "passive"))
      (node (ref "IC2") (pin "17") (pinfunction "3V3OUT_17") (pintype "output"))
    )
    (net (code "47") (name "Net-(IC2-USBDM)") (class "Default")
      (node (ref "IC2") (pin "16") (pinfunction "USBDM_16") (pintype "bidirectional"))
      (node (ref "X3") (pin "2") (pinfunction "2_2") (pintype "passive"))
    )
    (net (code "48") (name "Net-(IC2-USBDP)") (class "Default")
      (node (ref "IC2") (pin "15") (pinfunction "USBDP_15") (pintype "bidirectional"))
      (node (ref "X3") (pin "3") (pinfunction "3_3") (pintype "passive"))
    )
    (net (code "49") (name "Net-(IC3-(PCINT10{slash}INT2{slash}AIN0)PB2)") (class "Default")
      (node (ref "IC3") (pin "42") (pinfunction "(PCINT10/INT2/AIN0)PB2_42") (pintype "bidirectional"))
      (node (ref "R33") (pin "2") (pinfunction "2_2") (pintype "passive"))
    )
    (net (code "50") (name "Net-(IC3-(PCINT30{slash}OC2B{slash}ICP)PD6)") (class "Default")
      (node (ref "IC3") (pin "15") (pinfunction "(PCINT30/OC2B/ICP)PD6_15") (pintype "bidirectional"))
      (node (ref "SV6") (pin "5") (pinfunction "5_5") (pintype "passive"))
    )
    (net (code "51") (name "Net-(IC3-(PCINT31{slash}OC2A)PD7)") (class "Default")
      (node (ref "IC3") (pin "16") (pinfunction "(PCINT31/OC2A)PD7_16") (pintype "bidirectional"))
      (node (ref "SV6") (pin "3") (pinfunction "3_3") (pintype "passive"))
    )
    (net (code "52") (name "Net-(IC3-AREF)") (class "Default")
      (node (ref "C6") (pin "1") (pinfunction "1_1") (pintype "passive"))
      (node (ref "IC3") (pin "29") (pinfunction "AREF_29") (pintype "passive"))
    )
    (net (code "53") (name "Net-(IC3-XTAL1)") (class "Default")
      (node (ref "C9") (pin "1") (pinfunction "1_1") (pintype "passive"))
      (node (ref "IC3") (pin "8") (pinfunction "XTAL1_8") (pintype "bidirectional"))
      (node (ref "Q1") (pin "1") (pinfunction "1_1") (pintype "passive"))
    )
    (net (code "54") (name "Net-(IC3-XTAL2)") (class "Default")
      (node (ref "C8") (pin "1") (pinfunction "1_1") (pintype "passive"))
      (node (ref "IC3") (pin "7") (pinfunction "XTAL2_7") (pintype "bidirectional"))
      (node (ref "Q1") (pin "2") (pinfunction "2_2") (pintype "passive"))
    )
    (net (code "55") (name "Net-(IC4-CS)") (class "Default")
      (node (ref "IC4") (pin "7") (pinfunction "CS_7") (pintype "bidirectional"))
      (node (ref "R29") (pin "1") (pinfunction "1_1") (pintype "passive"))
      (node (ref "R30") (pin "1") (pinfunction "1_1") (pintype "passive"))
    )
    (net (code "56") (name "Net-(IC4-DIAGA)") (class "Default")
      (node (ref "IC4") (pin "6") (pinfunction "DIAGA_6") (pintype "open_collector"))
      (node (ref "R17") (pin "1") (pinfunction "1_1") (pintype "passive"))
      (node (ref "R20") (pin "2") (pinfunction "2_2") (pintype "passive"))
    )
    (net (code "57") (name "Net-(IC4-DIAGB)") (class "Default")
      (node (ref "IC4") (pin "10") (pinfunction "DIAGB_10") (pintype "open_collector"))
      (node (ref "R18") (pin "1") (pinfunction "1_1") (pintype "passive"))
      (node (ref "R19") (pin "1") (pinfunction "1_1") (pintype "passive"))
    )
    (net (code "58") (name "Net-(IC4-INA)") (class "Default")
      (node (ref "IC4") (pin "5") (pinfunction "INA_5") (pintype "input"))
      (node (ref "R13") (pin "1") (pinfunction "1_1") (pintype "passive"))
    )
    (net (code "59") (name "Net-(IC4-INB)") (class "Default")
      (node (ref "IC4") (pin "11") (pinfunction "INB_11") (pintype "input"))
      (node (ref "R14") (pin "1") (pinfunction "1_1") (pintype "passive"))
    )
    (net (code "60") (name "Net-(IC4-PWM)") (class "Default")
      (node (ref "IC4") (pin "8") (pinfunction "PWM_8") (pintype "input"))
      (node (ref "R16") (pin "1") (pinfunction "1_1") (pintype "passive"))
    )
    (net (code "61") (name "Net-(IC5-3V3OUT)") (class "Default")
      (node (ref "C23") (pin "1") (pinfunction "1_1") (pintype "passive"))
      (node (ref "IC5") (pin "17") (pinfunction "3V3OUT_17") (pintype "output"))
    )
    (net (code "62") (name "Net-(IC5-USBDM)") (class "Default")
      (node (ref "IC5") (pin "16") (pinfunction "USBDM_16") (pintype "bidirectional"))
      (node (ref "X5") (pin "2") (pinfunction "2_2") (pintype "passive"))
    )
    (net (code "63") (name "Net-(IC5-USBDP)") (class "Default")
      (node (ref "IC5") (pin "15") (pinfunction "USBDP_15") (pintype "bidirectional"))
      (node (ref "X5") (pin "3") (pinfunction "3_3") (pintype "passive"))
    )
    (net (code "64") (name "Net-(IC5-VCC)") (class "Default")
      (node (ref "C21") (pin "1") (pinfunction "1_1") (pintype "passive"))
      (node (ref "C22") (pin "+") (pinfunction "+_+") (pintype "passive"))
      (node (ref "IC5") (pin "20") (pinfunction "VCC_20") (pintype "power_in"))
      (node (ref "IC5") (pin "4") (pinfunction "VCCIO_4") (pintype "power_in"))
      (node (ref "L1") (pin "1") (pinfunction "1_1") (pintype "passive"))
      (node (ref "R10") (pin "2") (pinfunction "2_2") (pintype "passive"))
    )
    (net (code "65") (name "Net-(LED1-PadA)") (class "Default")
      (node (ref "LED1") (pin "A") (pinfunction "A_A") (pintype "passive"))
      (node (ref "R2") (pin "2") (pinfunction "2_2") (pintype "passive"))
    )
    (net (code "66") (name "Net-(LED2-PadA)") (class "Default")
      (node (ref "LED2") (pin "A") (pinfunction "A_A") (pintype "passive"))
      (node (ref "R5") (pin "2") (pinfunction "2_2") (pintype "passive"))
    )
    (net (code "67") (name "Net-(LED3-PadA)") (class "Default")
      (node (ref "LED3") (pin "A") (pinfunction "A_A") (pintype "passive"))
      (node (ref "R4") (pin "2") (pinfunction "2_2") (pintype "passive"))
    )
    (net (code "68") (name "Net-(LED4-PadA)") (class "Default")
      (node (ref "LED4") (pin "A") (pinfunction "A_A") (pintype "passive"))
      (node (ref "R3") (pin "2") (pinfunction "2_2") (pintype "passive"))
    )
    (net (code "69") (name "Net-(LED5-PadA)") (class "Default")
      (node (ref "LED5") (pin "A") (pinfunction "A_A") (pintype "passive"))
      (node (ref "R6") (pin "2") (pinfunction "2_2") (pintype "passive"))
    )
    (net (code "70") (name "Net-(LED6-PadA)") (class "Default")
      (node (ref "LED6") (pin "A") (pinfunction "A_A") (pintype "passive"))
      (node (ref "R7") (pin "2") (pinfunction "2_2") (pintype "passive"))
    )
    (net (code "71") (name "Net-(LED7-PadA)") (class "Default")
      (node (ref "LED7") (pin "A") (pinfunction "A_A") (pintype "passive"))
      (node (ref "R8") (pin "2") (pinfunction "2_2") (pintype "passive"))
    )
    (net (code "72") (name "Net-(LED8-PadA)") (class "Default")
      (node (ref "LED8") (pin "A") (pinfunction "A_A") (pintype "passive"))
      (node (ref "R9") (pin "2") (pinfunction "2_2") (pintype "passive"))
    )
    (net (code "73") (name "Net-(LED9-PadA)") (class "Default")
      (node (ref "LED9") (pin "A") (pinfunction "A_A") (pintype "passive"))
      (node (ref "R10") (pin "1") (pinfunction "1_1") (pintype "passive"))
    )
    (net (code "74") (name "Net-(Q2-G)") (class "Default")
      (node (ref "D1") (pin "C") (pinfunction "C_C") (pintype "passive"))
      (node (ref "Q2") (pin "1") (pinfunction "G_1") (pintype "passive"))
      (node (ref "R25") (pin "1") (pinfunction "1_1") (pintype "passive"))
    )
    (net (code "75") (name "Net-(Q2-S)") (class "Default")
      (node (ref "D1") (pin "A") (pinfunction "A_A") (pintype "passive"))
      (node (ref "IC4") (pin "18") (pinfunction "GNDB_18") (pintype "power_in"))
      (node (ref "IC4") (pin "19") (pinfunction "GNDB_19") (pintype "power_in"))
      (node (ref "IC4") (pin "20") (pinfunction "GNDB_20") (pintype "power_in"))
      (node (ref "IC4") (pin "26") (pinfunction "GNDA_26") (pintype "power_in"))
      (node (ref "IC4") (pin "27") (pinfunction "GNDA_27") (pintype "power_in"))
      (node (ref "IC4") (pin "28") (pinfunction "GNDA_28") (pintype "power_in"))
      (node (ref "Q2") (pin "3") (pinfunction "S_3") (pintype "passive"))
    )
    (net (code "76") (name "Net-(Q3-G)") (class "Default")
      (node (ref "D2") (pin "C") (pinfunction "C_C") (pintype "passive"))
      (node (ref "Q3") (pin "1") (pinfunction "G_1") (pintype "passive"))
      (node (ref "R26") (pin "1") (pinfunction "1_1") (pintype "passive"))
    )
    (net (code "77") (name "Net-(Q3-S)") (class "Default")
      (node (ref "D2") (pin "A") (pinfunction "A_A") (pintype "passive"))
      (node (ref "IC1") (pin "18") (pinfunction "GNDB_18") (pintype "power_in"))
      (node (ref "IC1") (pin "19") (pinfunction "GNDB_19") (pintype "power_in"))
      (node (ref "IC1") (pin "20") (pinfunction "GNDB_20") (pintype "power_in"))
      (node (ref "IC1") (pin "26") (pinfunction "GNDA_26") (pintype "power_in"))
      (node (ref "IC1") (pin "27") (pinfunction "GNDA_27") (pintype "power_in"))
      (node (ref "IC1") (pin "28") (pinfunction "GNDA_28") (pintype "power_in"))
      (node (ref "Q3") (pin "3") (pinfunction "S_3") (pintype "passive"))
    )
    (net (code "78") (name "Net-(R31-Pad1)") (class "Default")
      (node (ref "R31") (pin "1") (pinfunction "1_1") (pintype "passive"))
      (node (ref "R32") (pin "2") (pinfunction "2_2") (pintype "passive"))
      (node (ref "R33") (pin "1") (pinfunction "1_1") (pintype "passive"))
    )
    (net (code "79") (name "Net-(X1A-KL)") (class "Default")
      (node (ref "IC1") (pin "15") (pinfunction "OUTB_15") (pintype "output"))
      (node (ref "IC1") (pin "16") (pinfunction "OUTB_16") (pintype "passive"))
      (node (ref "IC1") (pin "21") (pinfunction "OUTB_21") (pintype "passive"))
      (node (ref "IC1") (pin "OUTB") (pinfunction "OUTB_OUTB") (pintype "passive"))
      (node (ref "IC1") (pin "OUTB@1") (pinfunction "OUTB_OUTB@1") (pintype "passive"))
      (node (ref "X1") (pin "1") (pinfunction "KL_1") (pintype "passive"))
    )
    (net (code "80") (name "Net-(X1B-KL)") (class "Default")
      (node (ref "IC1") (pin "1") (pinfunction "OUTA_1") (pintype "output"))
      (node (ref "IC1") (pin "25") (pinfunction "OUTA_25") (pintype "passive"))
      (node (ref "IC1") (pin "30") (pinfunction "OUTA_30") (pintype "passive"))
      (node (ref "IC1") (pin "OUTA") (pinfunction "OUTA_OUTA") (pintype "passive"))
      (node (ref "IC1") (pin "OUTA@1") (pinfunction "OUTA_OUTA@1") (pintype "passive"))
      (node (ref "X1") (pin "2") (pinfunction "KL_2") (pintype "passive"))
    )
    (net (code "81") (name "Net-(X2A-KL)") (class "Default")
      (node (ref "IC4") (pin "15") (pinfunction "OUTB_15") (pintype "output"))
      (node (ref "IC4") (pin "16") (pinfunction "OUTB_16") (pintype "passive"))
      (node (ref "IC4") (pin "21") (pinfunction "OUTB_21") (pintype "passive"))
      (node (ref "IC4") (pin "OUTB") (pinfunction "OUTB_OUTB") (pintype "passive"))
      (node (ref "IC4") (pin "OUTB@1") (pinfunction "OUTB_OUTB@1") (pintype "passive"))
      (node (ref "X2") (pin "1") (pinfunction "KL_1") (pintype "passive"))
    )
    (net (code "82") (name "Net-(X2B-KL)") (class "Default")
      (node (ref "IC4") (pin "1") (pinfunction "OUTA_1") (pintype "output"))
      (node (ref "IC4") (pin "25") (pinfunction "OUTA_25") (pintype "passive"))
      (node (ref "IC4") (pin "30") (pinfunction "OUTA_30") (pintype "passive"))
      (node (ref "IC4") (pin "OUTA") (pinfunction "OUTA_OUTA") (pintype "passive"))
      (node (ref "IC4") (pin "OUTA@1") (pinfunction "OUTA_OUTA@1") (pintype "passive"))
      (node (ref "X2") (pin "2") (pinfunction "KL_2") (pintype "passive"))
    )
    (net (code "83") (name "unconnected-(IC2-CBUS0-Pad23)") (class "Default")
      (node (ref "IC2") (pin "23") (pinfunction "CBUS0_23") (pintype "bidirectional"))
    )
    (net (code "84") (name "unconnected-(IC2-CBUS1-Pad22)") (class "Default")
      (node (ref "IC2") (pin "22") (pinfunction "CBUS1_22") (pintype "bidirectional"))
    )
    (net (code "85") (name "unconnected-(IC2-CBUS2-Pad13)") (class "Default")
      (node (ref "IC2") (pin "13") (pinfunction "CBUS2_13") (pintype "bidirectional"))
    )
    (net (code "86") (name "unconnected-(IC2-CBUS3-Pad14)") (class "Default")
      (node (ref "IC2") (pin "14") (pinfunction "CBUS3_14") (pintype "bidirectional"))
    )
    (net (code "87") (name "unconnected-(IC2-CBUS4-Pad12)") (class "Default")
      (node (ref "IC2") (pin "12") (pinfunction "CBUS4_12") (pintype "bidirectional"))
    )
    (net (code "88") (name "unconnected-(IC2-OSCI-Pad27)") (class "Default")
      (node (ref "IC2") (pin "27") (pinfunction "OSCI_27") (pintype "input"))
    )
    (net (code "89") (name "unconnected-(IC2-OSCO-Pad28)") (class "Default")
      (node (ref "IC2") (pin "28") (pinfunction "OSCO_28") (pintype "output"))
    )
    (net (code "90") (name "unconnected-(IC2-~{DCD}-Pad10)") (class "Default")
      (node (ref "IC2") (pin "10") (pinfunction "~{DCD}_10") (pintype "input"))
    )
    (net (code "91") (name "unconnected-(IC2-~{DSR}-Pad9)") (class "Default")
      (node (ref "IC2") (pin "9") (pinfunction "~{DSR}_9") (pintype "input"))
    )
    (net (code "92") (name "unconnected-(IC2-~{DTR}-Pad2)") (class "Default")
      (node (ref "IC2") (pin "2") (pinfunction "~{DTR}_2") (pintype "output"))
    )
    (net (code "93") (name "unconnected-(IC2-~{RESET}-Pad19)") (class "Default")
      (node (ref "IC2") (pin "19") (pinfunction "~{RESET}_19") (pintype "input"))
    )
    (net (code "94") (name "unconnected-(IC2-~{RI}-Pad6)") (class "Default")
      (node (ref "IC2") (pin "6") (pinfunction "~{RI}_6") (pintype "input"))
    )
    (net (code "95") (name "unconnected-(IC5-CBUS0-Pad23)") (class "Default")
      (node (ref "IC5") (pin "23") (pinfunction "CBUS0_23") (pintype "bidirectional"))
    )
    (net (code "96") (name "unconnected-(IC5-CBUS1-Pad22)") (class "Default")
      (node (ref "IC5") (pin "22") (pinfunction "CBUS1_22") (pintype "bidirectional"))
    )
    (net (code "97") (name "unconnected-(IC5-CBUS2-Pad13)") (class "Default")
      (node (ref "IC5") (pin "13") (pinfunction "CBUS2_13") (pintype "bidirectional"))
    )
    (net (code "98") (name "unconnected-(IC5-CBUS3-Pad14)") (class "Default")
      (node (ref "IC5") (pin "14") (pinfunction "CBUS3_14") (pintype "bidirectional"))
    )
    (net (code "99") (name "unconnected-(IC5-CBUS4-Pad12)") (class "Default")
      (node (ref "IC5") (pin "12") (pinfunction "CBUS4_12") (pintype "bidirectional"))
    )
    (net (code "100") (name "unconnected-(IC5-OSCI-Pad27)") (class "Default")
      (node (ref "IC5") (pin "27") (pinfunction "OSCI_27") (pintype "input"))
    )
    (net (code "101") (name "unconnected-(IC5-OSCO-Pad28)") (class "Default")
      (node (ref "IC5") (pin "28") (pinfunction "OSCO_28") (pintype "output"))
    )
    (net (code "102") (name "unconnected-(IC5-~{CTS}-Pad11)") (class "Default")
      (node (ref "IC5") (pin "11") (pinfunction "~{CTS}_11") (pintype "input"))
    )
    (net (code "103") (name "unconnected-(IC5-~{DCD}-Pad10)") (class "Default")
      (node (ref "IC5") (pin "10") (pinfunction "~{DCD}_10") (pintype "input"))
    )
    (net (code "104") (name "unconnected-(IC5-~{DSR}-Pad9)") (class "Default")
      (node (ref "IC5") (pin "9") (pinfunction "~{DSR}_9") (pintype "input"))
    )
    (net (code "105") (name "unconnected-(IC5-~{DTR}-Pad2)") (class "Default")
      (node (ref "IC5") (pin "2") (pinfunction "~{DTR}_2") (pintype "output"))
    )
    (net (code "106") (name "unconnected-(IC5-~{RESET}-Pad19)") (class "Default")
      (node (ref "IC5") (pin "19") (pinfunction "~{RESET}_19") (pintype "input"))
    )
    (net (code "107") (name "unconnected-(IC5-~{RI}-Pad6)") (class "Default")
      (node (ref "IC5") (pin "6") (pinfunction "~{RI}_6") (pintype "input"))
    )
    (net (code "108") (name "unconnected-(SV1-Pad7)") (class "Default")
      (node (ref "SV1") (pin "7") (pinfunction "7_7") (pintype "passive"))
    )
    (net (code "109") (name "unconnected-(SV2-Pad1)") (class "Default")
      (node (ref "SV2") (pin "1") (pinfunction "1_1") (pintype "passive"))
    )
    (net (code "110") (name "unconnected-(U$1-3VO-PadP$2)") (class "Default")
      (node (ref "U$1") (pin "P$2") (pinfunction "3VO_P$2") (pintype "bidirectional"))
    )
    (net (code "111") (name "unconnected-(U$1-ADR-PadP$10)") (class "Default")
      (node (ref "U$1") (pin "P$10") (pinfunction "ADR_P$10") (pintype "bidirectional"))
    )
    (net (code "112") (name "unconnected-(U$1-INT-PadP$9)") (class "Default")
      (node (ref "U$1") (pin "P$9") (pinfunction "INT_P$9") (pintype "bidirectional"))
    )
    (net (code "113") (name "unconnected-(U$1-PS0-PadP$7)") (class "Default")
      (node (ref "U$1") (pin "P$7") (pinfunction "PS0_P$7") (pintype "bidirectional"))
    )
    (net (code "114") (name "unconnected-(X3-PadS1)") (class "Default")
      (node (ref "X3") (pin "S1") (pinfunction "S1_S1") (pintype "passive"))
    )
    (net (code "115") (name "unconnected-(X3-PadS2)") (class "Default")
      (node (ref "X3") (pin "S2") (pinfunction "S2_S2") (pintype "passive"))
    )
    (net (code "116") (name "unconnected-(X5-PadS1)") (class "Default")
      (node (ref "X5") (pin "S1") (pinfunction "S1_S1") (pintype "passive"))
    )
    (net (code "117") (name "unconnected-(X5-PadS2)") (class "Default")
      (node (ref "X5") (pin "S2") (pinfunction "S2_S2") (pintype "passive"))
    )
  )
)
